# mapleCUx_large_041.net
KiCad netlist of a schematic drawn in EAGLE
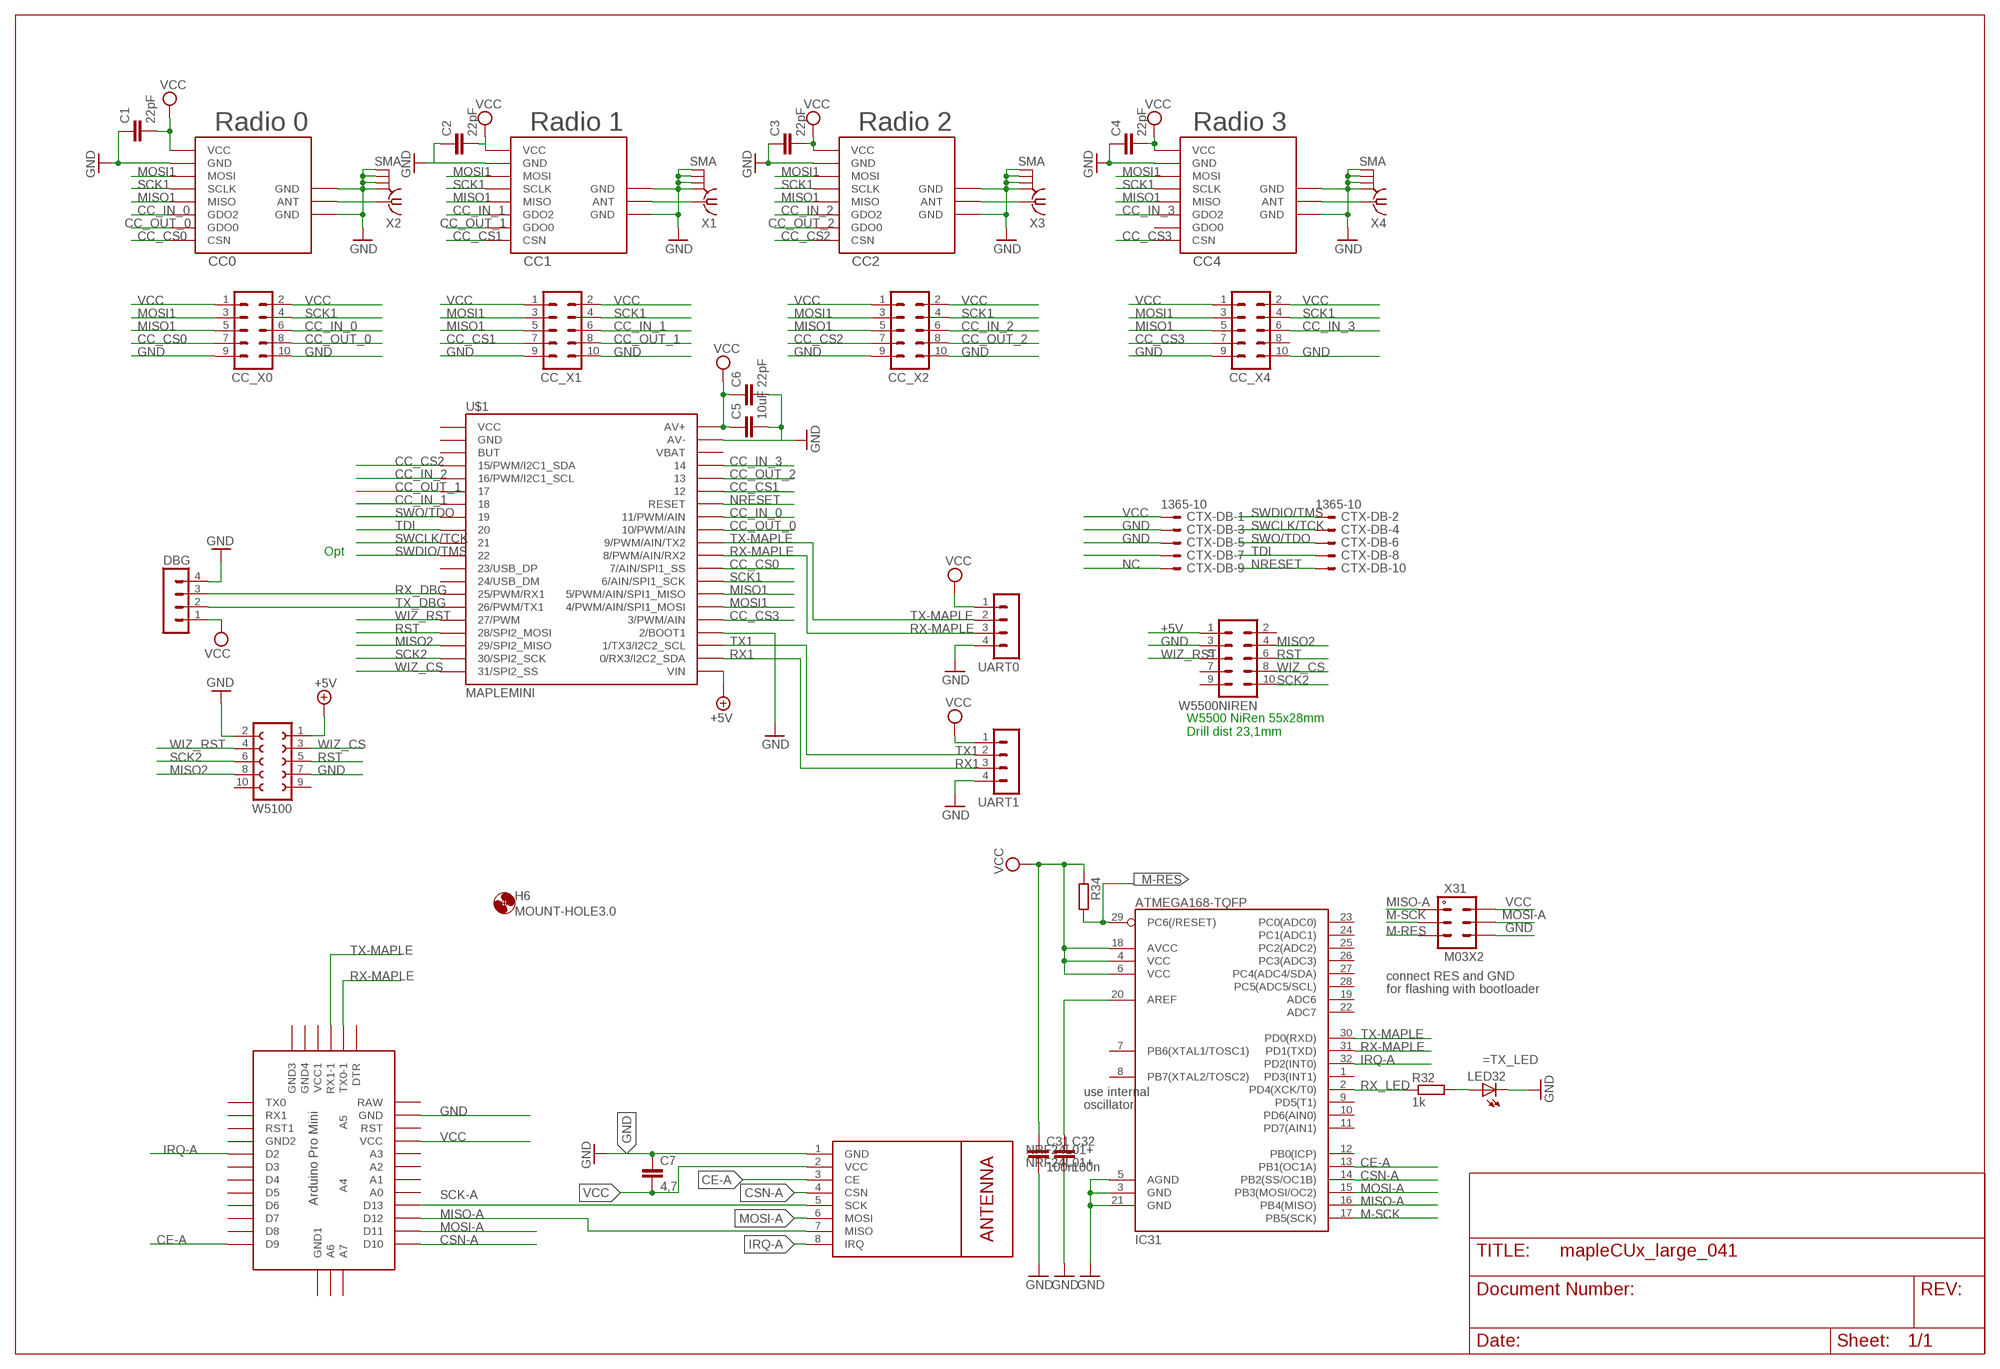
[diagram p0: schematic, sheet 1]

(export (version "E")
  (design (tool "Eeschema 10.0.6"))
  (components
    (comp (ref "C1")
      (value "22pF")
      (footprint "eagle-import:C0805")
      (libsource (lib "eagle-import") (part "C-EUC0805"))
    )
    (comp (ref "C2")
      (value "22pF")
      (footprint "eagle-import:C0805")
      (libsource (lib "eagle-import") (part "C-EUC0805"))
    )
    (comp (ref "C3")
      (value "22pF")
      (footprint "eagle-import:C0805")
      (libsource (lib "eagle-import") (part "C-EUC0805"))
    )
    (comp (ref "C4")
      (value "22pF")
      (footprint "eagle-import:C0805")
      (libsource (lib "eagle-import") (part "C-EUC0805"))
    )
    (comp (ref "C5")
      (value "10uF")
      (footprint "eagle-import:C1210")
      (libsource (lib "eagle-import") (part "C-EUC1210"))
    )
    (comp (ref "C6")
      (value "22pF")
      (footprint "eagle-import:C0805")
      (libsource (lib "eagle-import") (part "C-EUC0805"))
    )
    (comp (ref "C7")
      (value "4,7")
      (footprint "eagle-import:C1210")
      (libsource (lib "eagle-import") (part "C-EUC1210"))
    )
    (comp (ref "C31")
      (value "100n")
      (footprint "eagle-import:C0805")
      (libsource (lib "eagle-import") (part "C-EUC0805"))
    )
    (comp (ref "C32")
      (value "100n")
      (footprint "eagle-import:C0805")
      (libsource (lib "eagle-import") (part "C-EUC0805"))
    )
    (comp (ref "CC0")
      (value "CC1101_MODULE1SMD")
      (footprint "eagle-import:CC1101_MODULE1_SMD")
      (libsource (lib "eagle-import") (part "CC1101_MODULE1SMD"))
    )
    (comp (ref "CC1")
      (value "CC1101_MODULE1SMD")
      (footprint "eagle-import:CC1101_MODULE1_SMD")
      (libsource (lib "eagle-import") (part "CC1101_MODULE1SMD"))
    )
    (comp (ref "CC2")
      (value "CC1101_MODULE1SMD")
      (footprint "eagle-import:CC1101_MODULE1_SMD")
      (libsource (lib "eagle-import") (part "CC1101_MODULE1SMD"))
    )
    (comp (ref "CC4")
      (value "CC1101_MODULE1SMD")
      (footprint "eagle-import:CC1101_MODULE1_SMD")
      (libsource (lib "eagle-import") (part "CC1101_MODULE1SMD"))
    )
    (comp (ref "CC_X0")
      (value "MA05-2")
      (footprint "eagle-import:MA05-2")
      (libsource (lib "eagle-import") (part "MA05-2"))
    )
    (comp (ref "CC_X1")
      (value "MA05-2")
      (footprint "eagle-import:MA05-2")
      (libsource (lib "eagle-import") (part "MA05-2"))
    )
    (comp (ref "CC_X2")
      (value "MA05-2")
      (footprint "eagle-import:MA05-2")
      (libsource (lib "eagle-import") (part "MA05-2"))
    )
    (comp (ref "CC_X4")
      (value "MA05-2")
      (footprint "eagle-import:MA05-2")
      (libsource (lib "eagle-import") (part "MA05-2"))
    )
    (comp (ref "CTX-DB")
      (value "1365-10")
      (footprint "eagle-import:1365-10")
      (libsource (lib "eagle-import") (part "1365-10"))
    )
    (comp (ref "DBG")
      (value "MA04-1")
      (footprint "eagle-import:MA04-1")
      (libsource (lib "eagle-import") (part "MA04-1"))
    )
    (comp (ref "H6")
      (value "MOUNT-HOLE3.0")
      (footprint "eagle-import:3,0")
      (libsource (lib "eagle-import") (part "MOUNT-HOLE3.0"))
    )
    (comp (ref "IC31")
      (value "ATMEGA168-TQFP")
      (footprint "eagle-import:TQFP32-08")
      (libsource (lib "eagle-import") (part "ATMEGA168-TQFP"))
    )
    (comp (ref "LED32")
      (value "LEDCHIPLED_0805")
      (footprint "eagle-import:CHIPLED_0805")
      (libsource (lib "eagle-import") (part "LEDCHIPLED_0805"))
    )
    (comp (ref "NRF24L01+")
      (value "NRF24L01+")
      (footprint "eagle-import:WIRELESS-NRF24L01")
      (libsource (lib "eagle-import") (part "WIRELESS-NRF24L01"))
    )
    (comp (ref "R32")
      (value "1k")
      (footprint "eagle-import:R0805")
      (libsource (lib "eagle-import") (part "R-EU_R0805"))
    )
    (comp (ref "R34")
      (value "R-EU_R0805")
      (footprint "eagle-import:R0805")
      (libsource (lib "eagle-import") (part "R-EU_R0805"))
    )
    (comp (ref "U$1")
      (value "MAPLEMINI")
      (footprint "eagle-import:20-DIP")
      (libsource (lib "eagle-import") (part "MAPLEMINI"))
    )
    (comp (ref "U$2")
      (value "ABK-PRO-MINI")
      (footprint "eagle-import:ABK-PRO-MINI")
      (libsource (lib "eagle-import") (part "ABK-PRO-MINI"))
    )
    (comp (ref "UART0")
      (value "MA04-1")
      (footprint "eagle-import:MA04-1")
      (libsource (lib "eagle-import") (part "MA04-1"))
    )
    (comp (ref "UART1")
      (value "MA04-1")
      (footprint "eagle-import:MA04-1")
      (libsource (lib "eagle-import") (part "MA04-1"))
    )
    (comp (ref "W5100")
      (value "FE05-2")
      (footprint "eagle-import:FE05-2")
      (libsource (lib "eagle-import") (part "FE05-2"))
    )
    (comp (ref "W5500NIREN")
      (value "MA05-2")
      (footprint "eagle-import:MA05-2")
      (libsource (lib "eagle-import") (part "MA05-2"))
    )
    (comp (ref "X1")
      (value "SMA")
      (footprint "eagle-import:SMA")
      (libsource (lib "eagle-import") (part "SMA"))
    )
    (comp (ref "X2")
      (value "SMA")
      (footprint "eagle-import:SMA")
      (libsource (lib "eagle-import") (part "SMA"))
    )
    (comp (ref "X3")
      (value "SMA")
      (footprint "eagle-import:SMA")
      (libsource (lib "eagle-import") (part "SMA"))
    )
    (comp (ref "X4")
      (value "SMA")
      (footprint "eagle-import:SMA")
      (libsource (lib "eagle-import") (part "SMA"))
    )
    (comp (ref "X31")
      (value "M03X2")
      (footprint "eagle-import:2X03-1.27MM_SMD")
      (libsource (lib "eagle-import") (part "M03X2"))
    )
  )
  (nets
    (net (code "1") (name "+5V") (class "Default")
      (node (ref "U$1") (pin "21") (pinfunction "VIN_21") (pintype "bidirectional"))
      (node (ref "W5100") (pin "1") (pinfunction "1_1") (pintype "passive"))
      (node (ref "W5500NIREN") (pin "1") (pinfunction "1_1") (pintype "passive"))
    )
    (net (code "2") (name "/CC_CS0") (class "Default")
      (node (ref "CC0") (pin "CSN") (pinfunction "CSN_CSN") (pintype "bidirectional"))
      (node (ref "CC_X0") (pin "7") (pinfunction "7_7") (pintype "passive"))
      (node (ref "U$1") (pin "29") (pinfunction "7/AIN/SPI1_SS_29") (pintype "bidirectional"))
    )
    (net (code "3") (name "/CC_CS1") (class "Default")
      (node (ref "CC1") (pin "CSN") (pinfunction "CSN_CSN") (pintype "bidirectional"))
      (node (ref "CC_X1") (pin "7") (pinfunction "7_7") (pintype "passive"))
      (node (ref "U$1") (pin "35") (pinfunction "12_35") (pintype "bidirectional"))
    )
    (net (code "4") (name "/CC_CS2") (class "Default")
      (node (ref "CC2") (pin "CSN") (pinfunction "CSN_CSN") (pintype "bidirectional"))
      (node (ref "CC_X2") (pin "7") (pinfunction "7_7") (pintype "passive"))
      (node (ref "U$1") (pin "4") (pinfunction "15/PWM/I2C1_SDA_4") (pintype "bidirectional"))
    )
    (net (code "5") (name "/CC_CS3") (class "Default")
      (node (ref "CC4") (pin "CSN") (pinfunction "CSN_CSN") (pintype "bidirectional"))
      (node (ref "CC_X4") (pin "7") (pinfunction "7_7") (pintype "passive"))
      (node (ref "U$1") (pin "25") (pinfunction "3/PWM/AIN_25") (pintype "bidirectional"))
    )
    (net (code "6") (name "/CC_IN_0") (class "Default")
      (node (ref "CC0") (pin "GDO2") (pinfunction "GDO2_GDO2") (pintype "bidirectional"))
      (node (ref "CC_X0") (pin "6") (pinfunction "6_6") (pintype "passive"))
      (node (ref "U$1") (pin "33") (pinfunction "11/PWM/AIN_33") (pintype "bidirectional"))
    )
    (net (code "7") (name "/CC_IN_1") (class "Default")
      (node (ref "CC1") (pin "GDO2") (pinfunction "GDO2_GDO2") (pintype "bidirectional"))
      (node (ref "CC_X1") (pin "6") (pinfunction "6_6") (pintype "passive"))
      (node (ref "U$1") (pin "7") (pinfunction "18_7") (pintype "bidirectional"))
    )
    (net (code "8") (name "/CC_IN_2") (class "Default")
      (node (ref "CC2") (pin "GDO2") (pinfunction "GDO2_GDO2") (pintype "bidirectional"))
      (node (ref "CC_X2") (pin "6") (pinfunction "6_6") (pintype "passive"))
      (node (ref "U$1") (pin "5") (pinfunction "16/PWM/I2C1_SCL_5") (pintype "bidirectional"))
    )
    (net (code "9") (name "/CC_IN_3") (class "Default")
      (node (ref "CC4") (pin "GDO2") (pinfunction "GDO2_GDO2") (pintype "bidirectional"))
      (node (ref "CC_X4") (pin "6") (pinfunction "6_6") (pintype "passive"))
      (node (ref "U$1") (pin "37") (pinfunction "14_37") (pintype "bidirectional"))
    )
    (net (code "10") (name "/CC_OUT_0") (class "Default")
      (node (ref "CC0") (pin "GDO0") (pinfunction "GDO0_GDO0") (pintype "bidirectional"))
      (node (ref "CC_X0") (pin "8") (pinfunction "8_8") (pintype "passive"))
      (node (ref "U$1") (pin "32") (pinfunction "10/PWM/AIN_32") (pintype "bidirectional"))
    )
    (net (code "11") (name "/CC_OUT_1") (class "Default")
      (node (ref "CC1") (pin "GDO0") (pinfunction "GDO0_GDO0") (pintype "bidirectional"))
      (node (ref "CC_X1") (pin "8") (pinfunction "8_8") (pintype "passive"))
      (node (ref "U$1") (pin "6") (pinfunction "17_6") (pintype "bidirectional"))
    )
    (net (code "12") (name "/CC_OUT_2") (class "Default")
      (node (ref "CC2") (pin "GDO0") (pinfunction "GDO0_GDO0") (pintype "bidirectional"))
      (node (ref "CC_X2") (pin "8") (pinfunction "8_8") (pintype "passive"))
      (node (ref "U$1") (pin "36") (pinfunction "13_36") (pintype "bidirectional"))
    )
    (net (code "13") (name "/M-RES") (class "Default")
      (node (ref "IC31") (pin "29") (pinfunction "PC6(/RESET)_29") (pintype "bidirectional"))
      (node (ref "R34") (pin "2") (pinfunction "2_2") (pintype "passive"))
      (node (ref "X31") (pin "P$5") (pinfunction "5_P$5") (pintype "passive"))
    )
    (net (code "14") (name "/M-SCK") (class "Default")
      (node (ref "IC31") (pin "17") (pinfunction "PB5(SCK)_17") (pintype "bidirectional"))
      (node (ref "X31") (pin "P$3") (pinfunction "3_P$3") (pintype "passive"))
    )
    (net (code "15") (name "/MISO-A") (class "Default")
      (node (ref "IC31") (pin "16") (pinfunction "PB4(MISO)_16") (pintype "bidirectional"))
      (node (ref "NRF24L01+") (pin "7") (pinfunction "MISO_7") (pintype "bidirectional"))
      (node (ref "U$2") (pin "D12") (pinfunction "D12_D12") (pintype "bidirectional"))
      (node (ref "X31") (pin "P$1") (pinfunction "1_P$1") (pintype "passive"))
    )
    (net (code "16") (name "/MISO1") (class "Default")
      (node (ref "CC0") (pin "MISO") (pinfunction "MISO_MISO") (pintype "bidirectional"))
      (node (ref "CC1") (pin "MISO") (pinfunction "MISO_MISO") (pintype "bidirectional"))
      (node (ref "CC2") (pin "MISO") (pinfunction "MISO_MISO") (pintype "bidirectional"))
      (node (ref "CC4") (pin "MISO") (pinfunction "MISO_MISO") (pintype "bidirectional"))
      (node (ref "CC_X0") (pin "5") (pinfunction "5_5") (pintype "passive"))
      (node (ref "CC_X1") (pin "5") (pinfunction "5_5") (pintype "passive"))
      (node (ref "CC_X2") (pin "5") (pinfunction "5_5") (pintype "passive"))
      (node (ref "CC_X4") (pin "5") (pinfunction "5_5") (pintype "passive"))
      (node (ref "U$1") (pin "27") (pinfunction "5/PWM/AIN/SPI1_MISO_27") (pintype "bidirectional"))
    )
    (net (code "17") (name "/MISO2") (class "Default")
      (node (ref "U$1") (pin "18") (pinfunction "29/SPI2_MISO_18") (pintype "bidirectional"))
      (node (ref "W5100") (pin "8") (pinfunction "8_8") (pintype "passive"))
      (node (ref "W5500NIREN") (pin "4") (pinfunction "4_4") (pintype "passive"))
    )
    (net (code "18") (name "/MOSI1") (class "Default")
      (node (ref "CC0") (pin "MOSI") (pinfunction "MOSI_MOSI") (pintype "bidirectional"))
      (node (ref "CC1") (pin "MOSI") (pinfunction "MOSI_MOSI") (pintype "bidirectional"))
      (node (ref "CC2") (pin "MOSI") (pinfunction "MOSI_MOSI") (pintype "bidirectional"))
      (node (ref "CC4") (pin "MOSI") (pinfunction "MOSI_MOSI") (pintype "bidirectional"))
      (node (ref "CC_X0") (pin "3") (pinfunction "3_3") (pintype "passive"))
      (node (ref "CC_X1") (pin "3") (pinfunction "3_3") (pintype "passive"))
      (node (ref "CC_X2") (pin "3") (pinfunction "3_3") (pintype "passive"))
      (node (ref "CC_X4") (pin "3") (pinfunction "3_3") (pintype "passive"))
      (node (ref "U$1") (pin "26") (pinfunction "4/PWM/AIN/SPI1_MOSI_26") (pintype "bidirectional"))
    )
    (net (code "19") (name "/NC") (class "Default")
      (node (ref "CTX-DB") (pin "9") (pinfunction "S_9") (pintype "passive"))
    )
    (net (code "20") (name "/NRESET") (class "Default")
      (node (ref "CTX-DB") (pin "10") (pinfunction "S_10") (pintype "passive"))
      (node (ref "U$1") (pin "34") (pinfunction "RESET_34") (pintype "bidirectional"))
    )
    (net (code "21") (name "/RST") (class "Default")
      (node (ref "U$1") (pin "17") (pinfunction "28/SPI2_MOSI_17") (pintype "bidirectional"))
      (node (ref "W5100") (pin "5") (pinfunction "5_5") (pintype "passive"))
      (node (ref "W5500NIREN") (pin "6") (pinfunction "6_6") (pintype "passive"))
    )
    (net (code "22") (name "/RX-MAPLE") (class "Default")
      (node (ref "IC31") (pin "31") (pinfunction "PD1(TXD)_31") (pintype "bidirectional"))
      (node (ref "U$1") (pin "30") (pinfunction "8/PWM/AIN/RX2_30") (pintype "bidirectional"))
      (node (ref "U$2") (pin "TX0-1") (pinfunction "TX0-1_TX0-1") (pintype "bidirectional"))
      (node (ref "UART0") (pin "3") (pinfunction "3_3") (pintype "passive"))
    )
    (net (code "23") (name "/RX1") (class "Default")
      (node (ref "U$1") (pin "22") (pinfunction "0/RX3/I2C2_SDA_22") (pintype "bidirectional"))
      (node (ref "UART1") (pin "3") (pinfunction "3_3") (pintype "passive"))
    )
    (net (code "24") (name "/RX_DBG") (class "Default")
      (node (ref "DBG") (pin "3") (pinfunction "3_3") (pintype "passive"))
      (node (ref "U$1") (pin "14") (pinfunction "25/PWM/RX1_14") (pintype "bidirectional"))
    )
    (net (code "25") (name "/RX_LED") (class "Default")
      (node (ref "IC31") (pin "2") (pinfunction "PD4(XCK/T0)_2") (pintype "bidirectional"))
      (node (ref "R32") (pin "1") (pinfunction "1_1") (pintype "passive"))
    )
    (net (code "26") (name "/SCK-A") (class "Default")
      (node (ref "NRF24L01+") (pin "5") (pinfunction "SCK_5") (pintype "bidirectional"))
      (node (ref "U$2") (pin "D13") (pinfunction "D13_D13") (pintype "bidirectional"))
    )
    (net (code "27") (name "/SCK1") (class "Default")
      (node (ref "CC0") (pin "SCLK") (pinfunction "SCLK_SCLK") (pintype "bidirectional"))
      (node (ref "CC1") (pin "SCLK") (pinfunction "SCLK_SCLK") (pintype "bidirectional"))
      (node (ref "CC2") (pin "SCLK") (pinfunction "SCLK_SCLK") (pintype "bidirectional"))
      (node (ref "CC4") (pin "SCLK") (pinfunction "SCLK_SCLK") (pintype "bidirectional"))
      (node (ref "CC_X0") (pin "4") (pinfunction "4_4") (pintype "passive"))
      (node (ref "CC_X1") (pin "4") (pinfunction "4_4") (pintype "passive"))
      (node (ref "CC_X2") (pin "4") (pinfunction "4_4") (pintype "passive"))
      (node (ref "CC_X4") (pin "4") (pinfunction "4_4") (pintype "passive"))
      (node (ref "U$1") (pin "28") (pinfunction "6/AIN/SPI1_SCK_28") (pintype "bidirectional"))
    )
    (net (code "28") (name "/SCK2") (class "Default")
      (node (ref "U$1") (pin "19") (pinfunction "30/SPI2_SCK_19") (pintype "bidirectional"))
      (node (ref "W5100") (pin "6") (pinfunction "6_6") (pintype "passive"))
      (node (ref "W5500NIREN") (pin "10") (pinfunction "10_10") (pintype "passive"))
    )
    (net (code "29") (name "/SWCLK{slash}TCK") (class "Default")
      (node (ref "CTX-DB") (pin "4") (pinfunction "S_4") (pintype "passive"))
      (node (ref "U$1") (pin "10") (pinfunction "21_10") (pintype "bidirectional"))
    )
    (net (code "30") (name "/SWDIO{slash}TMS") (class "Default")
      (node (ref "CTX-DB") (pin "2") (pinfunction "S_2") (pintype "passive"))
      (node (ref "U$1") (pin "11") (pinfunction "22_11") (pintype "bidirectional"))
    )
    (net (code "31") (name "/SWO{slash}TDO") (class "Default")
      (node (ref "CTX-DB") (pin "6") (pinfunction "S_6") (pintype "passive"))
      (node (ref "U$1") (pin "8") (pinfunction "19_8") (pintype "bidirectional"))
    )
    (net (code "32") (name "/TDI") (class "Default")
      (node (ref "CTX-DB") (pin "8") (pinfunction "S_8") (pintype "passive"))
      (node (ref "U$1") (pin "9") (pinfunction "20_9") (pintype "bidirectional"))
    )
    (net (code "33") (name "/TX-MAPLE") (class "Default")
      (node (ref "IC31") (pin "30") (pinfunction "PD0(RXD)_30") (pintype "bidirectional"))
      (node (ref "U$1") (pin "31") (pinfunction "9/PWM/AIN/TX2_31") (pintype "bidirectional"))
      (node (ref "U$2") (pin "RX1-1") (pinfunction "RX1-1_RX1-1") (pintype "bidirectional"))
      (node (ref "UART0") (pin "2") (pinfunction "2_2") (pintype "passive"))
    )
    (net (code "34") (name "/TX1") (class "Default")
      (node (ref "U$1") (pin "23") (pinfunction "1/TX3/I2C2_SCL_23") (pintype "bidirectional"))
      (node (ref "UART1") (pin "2") (pinfunction "2_2") (pintype "passive"))
    )
    (net (code "35") (name "/TX_DBG") (class "Default")
      (node (ref "DBG") (pin "2") (pinfunction "2_2") (pintype "passive"))
      (node (ref "U$1") (pin "15") (pinfunction "26/PWM/TX1_15") (pintype "bidirectional"))
    )
    (net (code "36") (name "/WIZ_CS") (class "Default")
      (node (ref "U$1") (pin "20") (pinfunction "31/SPI2_SS_20") (pintype "bidirectional"))
      (node (ref "W5100") (pin "3") (pinfunction "3_3") (pintype "passive"))
      (node (ref "W5500NIREN") (pin "8") (pinfunction "8_8") (pintype "passive"))
    )
    (net (code "37") (name "/WIZ_RST") (class "Default")
      (node (ref "U$1") (pin "16") (pinfunction "27/PWM_16") (pintype "bidirectional"))
      (node (ref "W5100") (pin "4") (pinfunction "4_4") (pintype "passive"))
      (node (ref "W5500NIREN") (pin "5") (pinfunction "5_5") (pintype "passive"))
    )
    (net (code "38") (name "CE-A") (class "Default")
      (node (ref "IC31") (pin "13") (pinfunction "PB1(OC1A)_13") (pintype "bidirectional"))
      (node (ref "NRF24L01+") (pin "3") (pinfunction "CE_3") (pintype "bidirectional"))
      (node (ref "U$2") (pin "D9") (pinfunction "D9_D9") (pintype "bidirectional"))
    )
    (net (code "39") (name "CSN-A") (class "Default")
      (node (ref "IC31") (pin "14") (pinfunction "PB2(SS/OC1B)_14") (pintype "bidirectional"))
      (node (ref "NRF24L01+") (pin "4") (pinfunction "CSN_4") (pintype "bidirectional"))
      (node (ref "U$2") (pin "D10") (pinfunction "D10_D10") (pintype "bidirectional"))
    )
    (net (code "40") (name "GND") (class "Default")
      (node (ref "C1") (pin "1") (pinfunction "1_1") (pintype "passive"))
      (node (ref "C2") (pin "1") (pinfunction "1_1") (pintype "passive"))
      (node (ref "C3") (pin "1") (pinfunction "1_1") (pintype "passive"))
      (node (ref "C31") (pin "2") (pinfunction "2_2") (pintype "passive"))
      (node (ref "C32") (pin "2") (pinfunction "2_2") (pintype "passive"))
      (node (ref "C4") (pin "1") (pinfunction "1_1") (pintype "passive"))
      (node (ref "C5") (pin "2") (pinfunction "2_2") (pintype "passive"))
      (node (ref "C6") (pin "2") (pinfunction "2_2") (pintype "passive"))
      (node (ref "C7") (pin "1") (pinfunction "1_1") (pintype "passive"))
      (node (ref "CC0") (pin "GND@0") (pinfunction "GND_GND@0") (pintype "power_in"))
      (node (ref "CC0") (pin "GND@1") (pinfunction "GND_GND@1") (pintype "power_in"))
      (node (ref "CC0") (pin "GND@2") (pinfunction "GND_GND@2") (pintype "power_in"))
      (node (ref "CC1") (pin "GND@0") (pinfunction "GND_GND@0") (pintype "power_in"))
      (node (ref "CC1") (pin "GND@1") (pinfunction "GND_GND@1") (pintype "power_in"))
      (node (ref "CC1") (pin "GND@2") (pinfunction "GND_GND@2") (pintype "power_in"))
      (node (ref "CC2") (pin "GND@0") (pinfunction "GND_GND@0") (pintype "power_in"))
      (node (ref "CC2") (pin "GND@1") (pinfunction "GND_GND@1") (pintype "power_in"))
      (node (ref "CC2") (pin "GND@2") (pinfunction "GND_GND@2") (pintype "power_in"))
      (node (ref "CC4") (pin "GND@0") (pinfunction "GND_GND@0") (pintype "power_in"))
      (node (ref "CC4") (pin "GND@1") (pinfunction "GND_GND@1") (pintype "power_in"))
      (node (ref "CC4") (pin "GND@2") (pinfunction "GND_GND@2") (pintype "power_in"))
      (node (ref "CC_X0") (pin "10") (pinfunction "10_10") (pintype "passive"))
      (node (ref "CC_X0") (pin "9") (pinfunction "9_9") (pintype "passive"))
      (node (ref "CC_X1") (pin "10") (pinfunction "10_10") (pintype "passive"))
      (node (ref "CC_X1") (pin "9") (pinfunction "9_9") (pintype "passive"))
      (node (ref "CC_X2") (pin "10") (pinfunction "10_10") (pintype "passive"))
      (node (ref "CC_X2") (pin "9") (pinfunction "9_9") (pintype "passive"))
      (node (ref "CC_X4") (pin "10") (pinfunction "10_10") (pintype "passive"))
      (node (ref "CC_X4") (pin "9") (pinfunction "9_9") (pintype "passive"))
      (node (ref "CTX-DB") (pin "3") (pinfunction "S_3") (pintype "passive"))
      (node (ref "CTX-DB") (pin "5") (pinfunction "S_5") (pintype "passive"))
      (node (ref "DBG") (pin "4") (pinfunction "4_4") (pintype "passive"))
      (node (ref "IC31") (pin "21") (pinfunction "GND_21") (pintype "bidirectional"))
      (node (ref "IC31") (pin "3") (pinfunction "GND_3") (pintype "bidirectional"))
      (node (ref "IC31") (pin "5") (pinfunction "AGND_5") (pintype "bidirectional"))
      (node (ref "LED32") (pin "C") (pinfunction "C_C") (pintype "passive"))
      (node (ref "NRF24L01+") (pin "1") (pinfunction "GND_1") (pintype "power_in"))
      (node (ref "U$1") (pin "24") (pinfunction "2/BOOT1_24") (pintype "bidirectional"))
      (node (ref "U$1") (pin "39") (pinfunction "AV-_39") (pintype "bidirectional"))
      (node (ref "U$2") (pin "GND") (pinfunction "GND_GND") (pintype "bidirectional"))
      (node (ref "UART0") (pin "4") (pinfunction "4_4") (pintype "passive"))
      (node (ref "UART1") (pin "4") (pinfunction "4_4") (pintype "passive"))
      (node (ref "W5100") (pin "2") (pinfunction "2_2") (pintype "passive"))
      (node (ref "W5100") (pin "7") (pinfunction "7_7") (pintype "passive"))
      (node (ref "W5500NIREN") (pin "3") (pinfunction "3_3") (pintype "passive"))
      (node (ref "X1") (pin "GND@1") (pinfunction "2_GND@1") (pintype "passive"))
      (node (ref "X1") (pin "GND@2") (pinfunction "3_GND@2") (pintype "passive"))
      (node (ref "X1") (pin "GND@3") (pinfunction "4_GND@3") (pintype "passive"))
      (node (ref "X1") (pin "GND@4") (pinfunction "5_GND@4") (pintype "passive"))
      (node (ref "X2") (pin "GND@1") (pinfunction "2_GND@1") (pintype "passive"))
      (node (ref "X2") (pin "GND@2") (pinfunction "3_GND@2") (pintype "passive"))
      (node (ref "X2") (pin "GND@3") (pinfunction "4_GND@3") (pintype "passive"))
      (node (ref "X2") (pin "GND@4") (pinfunction "5_GND@4") (pintype "passive"))
      (node (ref "X3") (pin "GND@1") (pinfunction "2_GND@1") (pintype "passive"))
      (node (ref "X3") (pin "GND@2") (pinfunction "3_GND@2") (pintype "passive"))
      (node (ref "X3") (pin "GND@3") (pinfunction "4_GND@3") (pintype "passive"))
      (node (ref "X3") (pin "GND@4") (pinfunction "5_GND@4") (pintype "passive"))
      (node (ref "X31") (pin "P$6") (pinfunction "6_P$6") (pintype "passive"))
      (node (ref "X4") (pin "GND@1") (pinfunction "2_GND@1") (pintype "passive"))
      (node (ref "X4") (pin "GND@2") (pinfunction "3_GND@2") (pintype "passive"))
      (node (ref "X4") (pin "GND@3") (pinfunction "4_GND@3") (pintype "passive"))
      (node (ref "X4") (pin "GND@4") (pinfunction "5_GND@4") (pintype "passive"))
    )
    (net (code "41") (name "IRQ-A") (class "Default")
      (node (ref "IC31") (pin "32") (pinfunction "PD2(INT0)_32") (pintype "bidirectional"))
      (node (ref "NRF24L01+") (pin "8") (pinfunction "IRQ_8") (pintype "bidirectional"))
      (node (ref "U$2") (pin "D2") (pinfunction "D2_D2") (pintype "bidirectional"))
    )
    (net (code "42") (name "MOSI-A") (class "Default")
      (node (ref "IC31") (pin "15") (pinfunction "PB3(MOSI/OC2)_15") (pintype "bidirectional"))
      (node (ref "NRF24L01+") (pin "6") (pinfunction "MOSI_6") (pintype "bidirectional"))
      (node (ref "U$2") (pin "D11") (pinfunction "D11_D11") (pintype "bidirectional"))
      (node (ref "X31") (pin "P$4") (pinfunction "4_P$4") (pintype "passive"))
    )
    (net (code "43") (name "Net-(CC0-PadANT)") (class "Default")
      (node (ref "CC0") (pin "ANT") (pinfunction "ANT_ANT") (pintype "output"))
      (node (ref "X2") (pin "1") (pinfunction "1_1") (pintype "passive"))
    )
    (net (code "44") (name "Net-(CC1-PadANT)") (class "Default")
      (node (ref "CC1") (pin "ANT") (pinfunction "ANT_ANT") (pintype "output"))
      (node (ref "X1") (pin "1") (pinfunction "1_1") (pintype "passive"))
    )
    (net (code "45") (name "Net-(CC2-PadANT)") (class "Default")
      (node (ref "CC2") (pin "ANT") (pinfunction "ANT_ANT") (pintype "output"))
      (node (ref "X3") (pin "1") (pinfunction "1_1") (pintype "passive"))
    )
    (net (code "46") (name "Net-(CC4-PadANT)") (class "Default")
      (node (ref "CC4") (pin "ANT") (pinfunction "ANT_ANT") (pintype "output"))
      (node (ref "X4") (pin "1") (pinfunction "1_1") (pintype "passive"))
    )
    (net (code "47") (name "Net-(IC31-AREF)") (class "Default")
      (node (ref "C32") (pin "1") (pinfunction "1_1") (pintype "passive"))
      (node (ref "IC31") (pin "20") (pinfunction "AREF_20") (pintype "bidirectional"))
    )
    (net (code "48") (name "Net-(LED32-PadA)") (class "Default")
      (node (ref "LED32") (pin "A") (pinfunction "A_A") (pintype "passive"))
      (node (ref "R32") (pin "2") (pinfunction "2_2") (pintype "passive"))
    )
    (net (code "49") (name "VCC") (class "Default")
      (node (ref "C1") (pin "2") (pinfunction "2_2") (pintype "passive"))
      (node (ref "C2") (pin "2") (pinfunction "2_2") (pintype "passive"))
      (node (ref "C3") (pin "2") (pinfunction "2_2") (pintype "passive"))
      (node (ref "C31") (pin "1") (pinfunction "1_1") (pintype "passive"))
      (node (ref "C4") (pin "2") (pinfunction "2_2") (pintype "passive"))
      (node (ref "C5") (pin "1") (pinfunction "1_1") (pintype "passive"))
      (node (ref "C6") (pin "1") (pinfunction "1_1") (pintype "passive"))
      (node (ref "C7") (pin "2") (pinfunction "2_2") (pintype "passive"))
      (node (ref "CC0") (pin "VCC") (pinfunction "VCC_VCC") (pintype "power_in"))
      (node (ref "CC1") (pin "VCC") (pinfunction "VCC_VCC") (pintype "power_in"))
      (node (ref "CC2") (pin "VCC") (pinfunction "VCC_VCC") (pintype "power_in"))
      (node (ref "CC4") (pin "VCC") (pinfunction "VCC_VCC") (pintype "power_in"))
      (node (ref "CC_X0") (pin "1") (pinfunction "1_1") (pintype "passive"))
      (node (ref "CC_X0") (pin "2") (pinfunction "2_2") (pintype "passive"))
      (node (ref "CC_X1") (pin "1") (pinfunction "1_1") (pintype "passive"))
      (node (ref "CC_X1") (pin "2") (pinfunction "2_2") (pintype "passive"))
      (node (ref "CC_X2") (pin "1") (pinfunction "1_1") (pintype "passive"))
      (node (ref "CC_X2") (pin "2") (pinfunction "2_2") (pintype "passive"))
      (node (ref "CC_X4") (pin "1") (pinfunction "1_1") (pintype "passive"))
      (node (ref "CC_X4") (pin "2") (pinfunction "2_2") (pintype "passive"))
      (node (ref "CTX-DB") (pin "1") (pinfunction "S_1") (pintype "passive"))
      (node (ref "DBG") (pin "1") (pinfunction "1_1") (pintype "passive"))
      (node (ref "IC31") (pin "18") (pinfunction "AVCC_18") (pintype "bidirectional"))
      (node (ref "IC31") (pin "4") (pinfunction "VCC_4") (pintype "bidirectional"))
      (node (ref "IC31") (pin "6") (pinfunction "VCC_6") (pintype "bidirectional"))
      (node (ref "NRF24L01+") (pin "2") (pinfunction "VCC_2") (pintype "power_in"))
      (node (ref "R34") (pin "1") (pinfunction "1_1") (pintype "passive"))
      (node (ref "U$1") (pin "40") (pinfunction "AV+_40") (pintype "bidirectional"))
      (node (ref "U$2") (pin "VCC") (pinfunction "VCC_VCC") (pintype "bidirectional"))
      (node (ref "UART0") (pin "1") (pinfunction "1_1") (pintype "passive"))
      (node (ref "UART1") (pin "1") (pinfunction "1_1") (pintype "passive"))
      (node (ref "X31") (pin "P$2") (pinfunction "2_P$2") (pintype "passive"))
    )
    (net (code "50") (name "unconnected-(CC4-PadGDO0)") (class "Default")
      (node (ref "CC4") (pin "GDO0") (pinfunction "GDO0_GDO0") (pintype "bidirectional"))
    )
    (net (code "51") (name "unconnected-(CC_X4-Pad8)") (class "Default")
      (node (ref "CC_X4") (pin "8") (pinfunction "8_8") (pintype "passive"))
    )
    (net (code "52") (name "unconnected-(CTX-DBH-S-Pad7)") (class "Default")
      (node (ref "CTX-DB") (pin "7") (pinfunction "S_7") (pintype "passive"))
    )
    (net (code "53") (name "unconnected-(IC31-ADC6-Pad19)") (class "Default")
      (node (ref "IC31") (pin "19") (pinfunction "ADC6_19") (pintype "bidirectional"))
    )
    (net (code "54") (name "unconnected-(IC31-ADC7-Pad22)") (class "Default")
      (node (ref "IC31") (pin "22") (pinfunction "ADC7_22") (pintype "bidirectional"))
    )
    (net (code "55") (name "unconnected-(IC31-PB0(ICP)-Pad12)") (class "Default")
      (node (ref "IC31") (pin "12") (pinfunction "PB0(ICP)_12") (pintype "bidirectional"))
    )
    (net (code "56") (name "unconnected-(IC31-PB6(XTAL1{slash}TOSC1)-Pad7)") (class "Default")
      (node (ref "IC31") (pin "7") (pinfunction "PB6(XTAL1/TOSC1)_7") (pintype "bidirectional"))
    )
    (net (code "57") (name "unconnected-(IC31-PB7(XTAL2{slash}TOSC2)-Pad8)") (class "Default")
      (node (ref "IC31") (pin "8") (pinfunction "PB7(XTAL2/TOSC2)_8") (pintype "bidirectional"))
    )
    (net (code "58") (name "unconnected-(IC31-PC0(ADC0)-Pad23)") (class "Default")
      (node (ref "IC31") (pin "23") (pinfunction "PC0(ADC0)_23") (pintype "bidirectional"))
    )
    (net (code "59") (name "unconnected-(IC31-PC1(ADC1)-Pad24)") (class "Default")
      (node (ref "IC31") (pin "24") (pinfunction "PC1(ADC1)_24") (pintype "bidirectional"))
    )
    (net (code "60") (name "unconnected-(IC31-PC2(ADC2)-Pad25)") (class "Default")
      (node (ref "IC31") (pin "25") (pinfunction "PC2(ADC2)_25") (pintype "bidirectional"))
    )
    (net (code "61") (name "unconnected-(IC31-PC3(ADC3)-Pad26)") (class "Default")
      (node (ref "IC31") (pin "26") (pinfunction "PC3(ADC3)_26") (pintype "bidirectional"))
    )
    (net (code "62") (name "unconnected-(IC31-PC4(ADC4{slash}SDA)-Pad27)") (class "Default")
      (node (ref "IC31") (pin "27") (pinfunction "PC4(ADC4/SDA)_27") (pintype "bidirectional"))
    )
    (net (code "63") (name "unconnected-(IC31-PC5(ADC5{slash}SCL)-Pad28)") (class "Default")
      (node (ref "IC31") (pin "28") (pinfunction "PC5(ADC5/SCL)_28") (pintype "bidirectional"))
    )
    (net (code "64") (name "unconnected-(IC31-PD3(INT1)-Pad1)") (class "Default")
      (node (ref "IC31") (pin "1") (pinfunction "PD3(INT1)_1") (pintype "bidirectional"))
    )
    (net (code "65") (name "unconnected-(IC31-PD5(T1)-Pad9)") (class "Default")
      (node (ref "IC31") (pin "9") (pinfunction "PD5(T1)_9") (pintype "bidirectional"))
    )
    (net (code "66") (name "unconnected-(IC31-PD6(AIN0)-Pad10)") (class "Default")
      (node (ref "IC31") (pin "10") (pinfunction "PD6(AIN0)_10") (pintype "bidirectional"))
    )
    (net (code "67") (name "unconnected-(IC31-PD7(AIN1)-Pad11)") (class "Default")
      (node (ref "IC31") (pin "11") (pinfunction "PD7(AIN1)_11") (pintype "bidirectional"))
    )
    (net (code "68") (name "unconnected-(U$1-23{slash}USB_DP-Pad12)") (class "Default")
      (node (ref "U$1") (pin "12") (pinfunction "23/USB_DP_12") (pintype "bidirectional"))
    )
    (net (code "69") (name "unconnected-(U$1-24{slash}USB_DM-Pad13)") (class "Default")
      (node (ref "U$1") (pin "13") (pinfunction "24/USB_DM_13") (pintype "bidirectional"))
    )
    (net (code "70") (name "unconnected-(U$1-BUT-Pad3)") (class "Default")
      (node (ref "U$1") (pin "3") (pinfunction "BUT_3") (pintype "bidirectional"))
    )
    (net (code "71") (name "unconnected-(U$1-GND-Pad2)") (class "Default")
      (node (ref "U$1") (pin "2") (pinfunction "GND_2") (pintype "bidirectional"))
    )
    (net (code "72") (name "unconnected-(U$1-VBAT-Pad38)") (class "Default")
      (node (ref "U$1") (pin "38") (pinfunction "VBAT_38") (pintype "bidirectional"))
    )
    (net (code "73") (name "unconnected-(U$1-VCC-Pad1)") (class "Default")
      (node (ref "U$1") (pin "1") (pinfunction "VCC_1") (pintype "bidirectional"))
    )
    (net (code "74") (name "unconnected-(U$2-GND1-PadGND4)") (class "Default")
      (node (ref "U$2") (pin "GND4") (pinfunction "GND1_GND4") (pintype "bidirectional"))
    )
    (net (code "75") (name "unconnected-(U$2-GND2-PadGND1)") (class "Default")
      (node (ref "U$2") (pin "GND1") (pinfunction "GND2_GND1") (pintype "bidirectional"))
    )
    (net (code "76") (name "unconnected-(U$2-GND3-PadGND2)") (class "Default")
      (node (ref "U$2") (pin "GND2") (pinfunction "GND3_GND2") (pintype "bidirectional"))
    )
    (net (code "77") (name "unconnected-(U$2-GND4-PadGND3)") (class "Default")
      (node (ref "U$2") (pin "GND3") (pinfunction "GND4_GND3") (pintype "bidirectional"))
    )
    (net (code "78") (name "unconnected-(U$2-PadA0)") (class "Default")
      (node (ref "U$2") (pin "A0") (pinfunction "A0_A0") (pintype "bidirectional"))
    )
    (net (code "79") (name "unconnected-(U$2-PadA1)") (class "Default")
      (node (ref "U$2") (pin "A1") (pinfunction "A1_A1") (pintype "bidirectional"))
    )
    (net (code "80") (name "unconnected-(U$2-PadA2)") (class "Default")
      (node (ref "U$2") (pin "A2") (pinfunction "A2_A2") (pintype "bidirectional"))
    )
    (net (code "81") (name "unconnected-(U$2-PadA3)") (class "Default")
      (node (ref "U$2") (pin "A3") (pinfunction "A3_A3") (pintype "bidirectional"))
    )
    (net (code "82") (name "unconnected-(U$2-PadA4)") (class "Default")
      (node (ref "U$2") (pin "A4") (pinfunction "A4_A4") (pintype "bidirectional"))
    )
    (net (code "83") (name "unconnected-(U$2-PadA5)") (class "Default")
      (node (ref "U$2") (pin "A5") (pinfunction "A5_A5") (pintype "bidirectional"))
    )
    (net (code "84") (name "unconnected-(U$2-PadA6)") (class "Default")
      (node (ref "U$2") (pin "A6") (pinfunction "A6_A6") (pintype "bidirectional"))
    )
    (net (code "85") (name "unconnected-(U$2-PadA7)") (class "Default")
      (node (ref "U$2") (pin "A7") (pinfunction "A7_A7") (pintype "bidirectional"))
    )
    (net (code "86") (name "unconnected-(U$2-PadD3)") (class "Default")
      (node (ref "U$2") (pin "D3") (pinfunction "D3_D3") (pintype "bidirectional"))
    )
    (net (code "87") (name "unconnected-(U$2-PadD4)") (class "Default")
      (node (ref "U$2") (pin "D4") (pinfunction "D4_D4") (pintype "bidirectional"))
    )
    (net (code "88") (name "unconnected-(U$2-PadD5)") (class "Default")
      (node (ref "U$2") (pin "D5") (pinfunction "D5_D5") (pintype "bidirectional"))
    )
    (net (code "89") (name "unconnected-(U$2-PadD6)") (class "Default")
      (node (ref "U$2") (pin "D6") (pinfunction "D6_D6") (pintype "bidirectional"))
    )
    (net (code "90") (name "unconnected-(U$2-PadD7)") (class "Default")
      (node (ref "U$2") (pin "D7") (pinfunction "D7_D7") (pintype "bidirectional"))
    )
    (net (code "91") (name "unconnected-(U$2-PadD8)") (class "Default")
      (node (ref "U$2") (pin "D8") (pinfunction "D8_D8") (pintype "bidirectional"))
    )
    (net (code "92") (name "unconnected-(U$2-PadDTR)") (class "Default")
      (node (ref "U$2") (pin "DTR") (pinfunction "DTR_DTR") (pintype "bidirectional"))
    )
    (net (code "93") (name "unconnected-(U$2-PadRAW)") (class "Default")
      (node (ref "U$2") (pin "RAW") (pinfunction "RAW_RAW") (pintype "bidirectional"))
    )
    (net (code "94") (name "unconnected-(U$2-PadRST)") (class "Default")
      (node (ref "U$2") (pin "RST") (pinfunction "RST_RST") (pintype "bidirectional"))
    )
    (net (code "95") (name "unconnected-(U$2-PadRST1)") (class "Default")
      (node (ref "U$2") (pin "RST1") (pinfunction "RST1_RST1") (pintype "bidirectional"))
    )
    (net (code "96") (name "unconnected-(U$2-PadRX1)") (class "Default")
      (node (ref "U$2") (pin "RX1") (pinfunction "RX1_RX1") (pintype "bidirectional"))
    )
    (net (code "97") (name "unconnected-(U$2-PadTX0)") (class "Default")
      (node (ref "U$2") (pin "TX0") (pinfunction "TX0_TX0") (pintype "bidirectional"))
    )
    (net (code "98") (name "unconnected-(U$2-PadVCC1)") (class "Default")
      (node (ref "U$2") (pin "VCC1") (pinfunction "VCC1_VCC1") (pintype "bidirectional"))
    )
    (net (code "99") (name "unconnected-(W5100-Pad9)") (class "Default")
      (node (ref "W5100") (pin "9") (pinfunction "9_9") (pintype "passive"))
    )
    (net (code "100") (name "unconnected-(W5100-Pad10)") (class "Default")
      (node (ref "W5100") (pin "10") (pinfunction "10_10") (pintype "passive"))
    )
    (net (code "101") (name "unconnected-(W5500NIREN-Pad2)") (class "Default")
      (node (ref "W5500NIREN") (pin "2") (pinfunction "2_2") (pintype "passive"))
    )
    (net (code "102") (name "unconnected-(W5500NIREN-Pad7)") (class "Default")
      (node (ref "W5500NIREN") (pin "7") (pinfunction "7_7") (pintype "passive"))
    )
    (net (code "103") (name "unconnected-(W5500NIREN-Pad9)") (class "Default")
      (node (ref "W5500NIREN") (pin "9") (pinfunction "9_9") (pintype "passive"))
    )
  )
)
